# 130609_ReceiverSTM_0_0.net
KiCad netlist of a schematic drawn in EAGLE
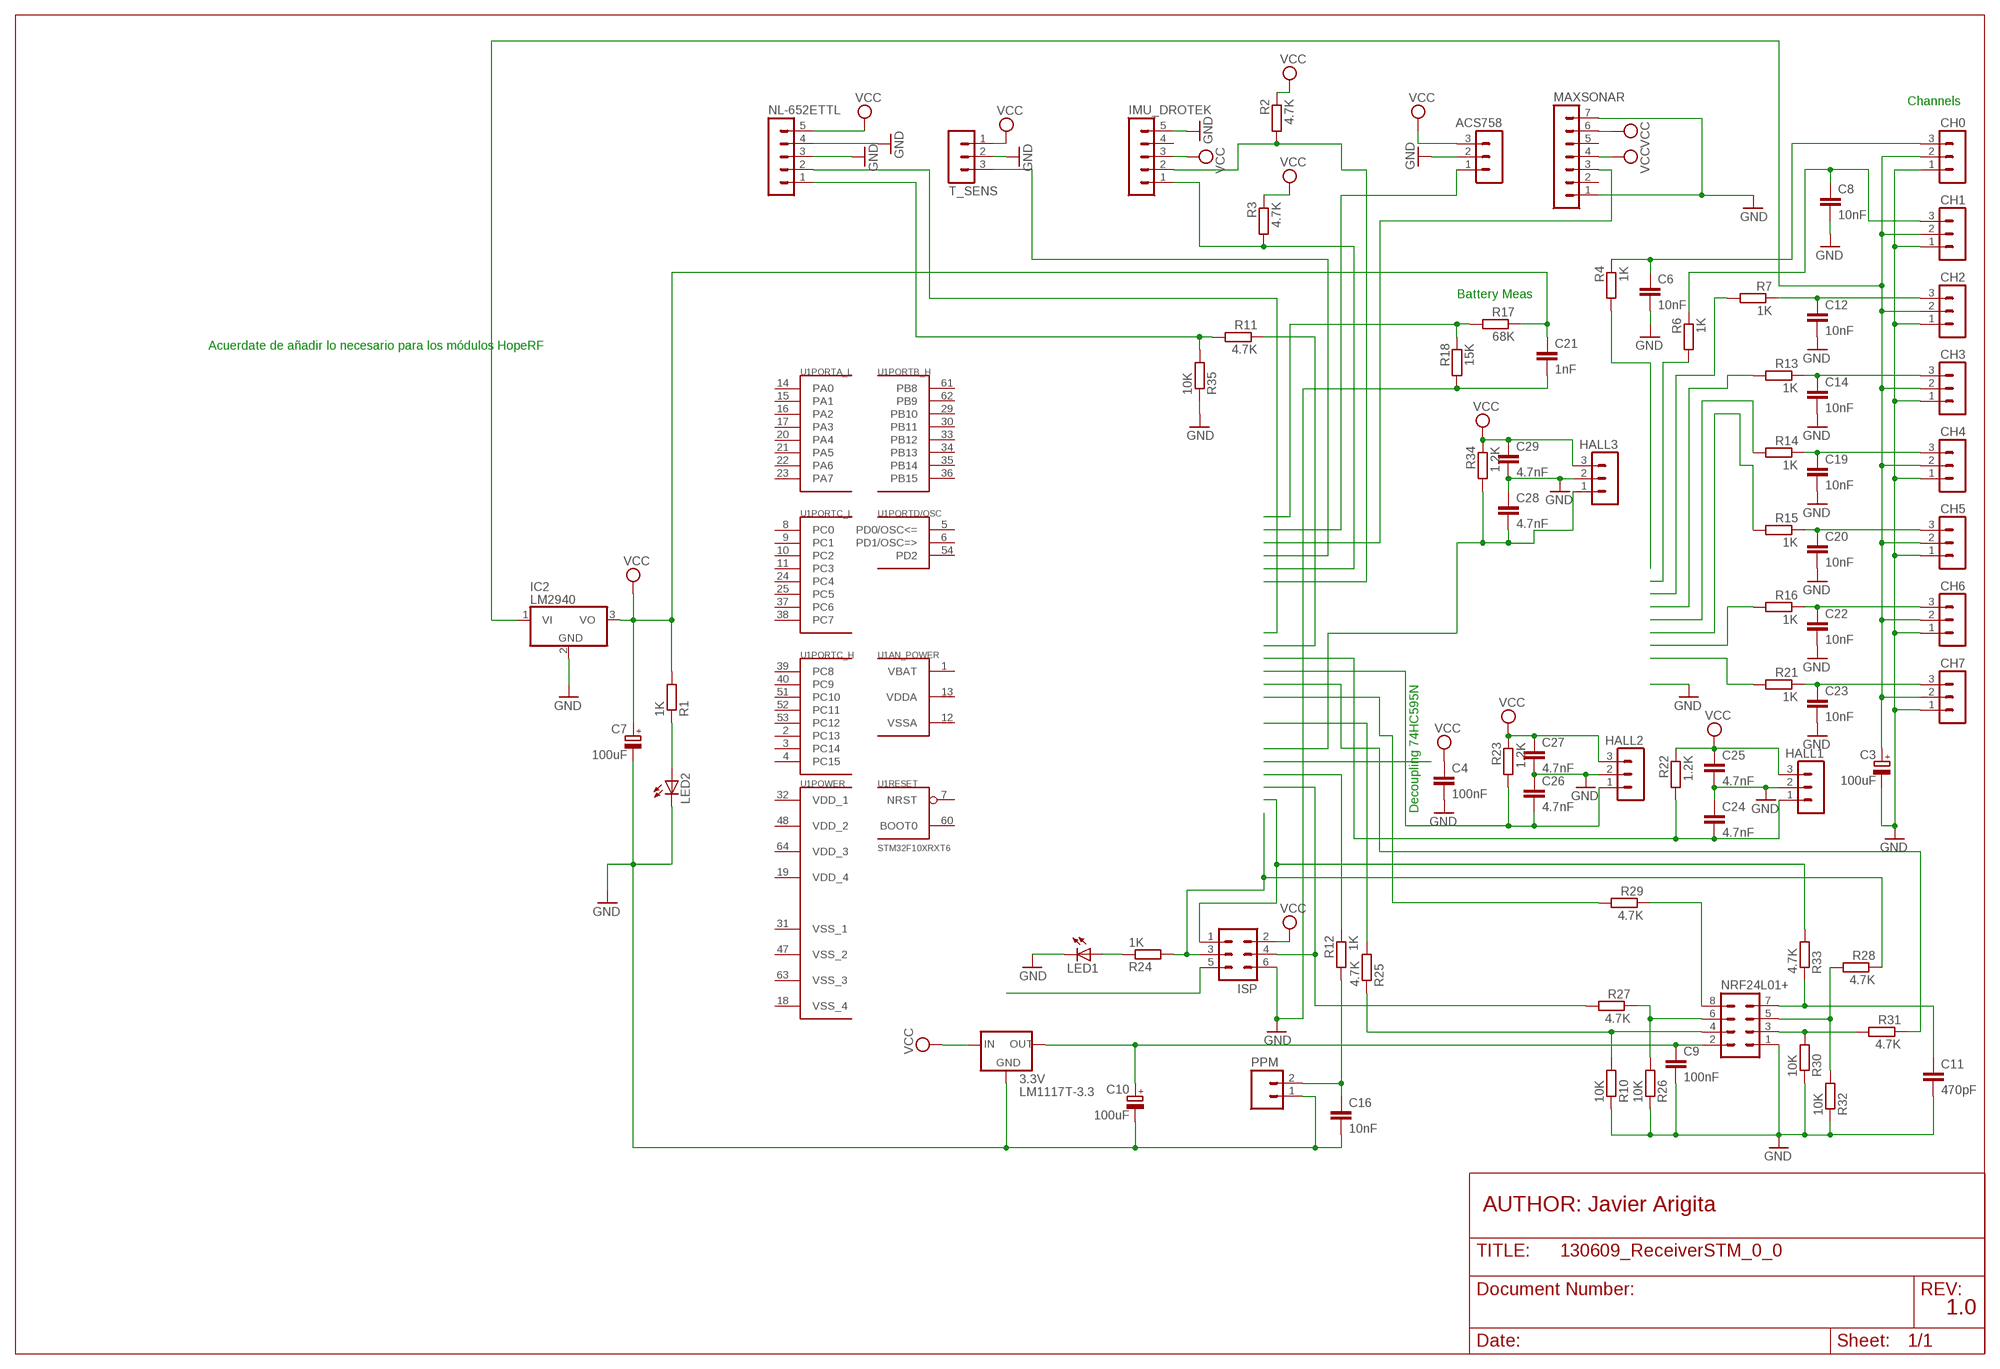
[diagram p0: schematic, sheet 1]

(export (version "E")
  (design (tool "Eeschema 10.0.6"))
  (components
    (comp (ref "3.3V")
      (value "LM1117T-3.3")
      (footprint "eagle-import:TO220")
      (libsource (lib "eagle-import") (part "LM1117T-3.3"))
    )
    (comp (ref "ACS758")
      (value "MA03-1")
      (footprint "eagle-import:MA03-1")
      (libsource (lib "eagle-import") (part "MA03-1"))
    )
    (comp (ref "C3")
      (value "100uF")
      (footprint "eagle-import:E2,5-6E")
      (libsource (lib "eagle-import") (part "CPOL-EUE2,5-6E"))
    )
    (comp (ref "C4")
      (value "100nF")
      (footprint "eagle-import:C050-025X075")
      (libsource (lib "eagle-import") (part "C-EU050-025X075"))
    )
    (comp (ref "C6")
      (value "10nF")
      (footprint "eagle-import:C025-030X050")
      (libsource (lib "eagle-import") (part "C-EU025-030X050"))
    )
    (comp (ref "C7")
      (value "100uF")
      (footprint "eagle-import:E2,5-6E")
      (libsource (lib "eagle-import") (part "CPOL-EUE2,5-6E"))
    )
    (comp (ref "C8")
      (value "10nF")
      (footprint "eagle-import:C025-030X050")
      (libsource (lib "eagle-import") (part "C-EU025-030X050"))
    )
    (comp (ref "C9")
      (value "100nF")
      (footprint "eagle-import:C050-025X075")
      (libsource (lib "eagle-import") (part "C-EU050-025X075"))
    )
    (comp (ref "C10")
      (value "100uF")
      (footprint "eagle-import:E2,5-6E")
      (libsource (lib "eagle-import") (part "CPOL-EUE2,5-6E"))
    )
    (comp (ref "C11")
      (value "470pF")
      (footprint "eagle-import:C025-030X050")
      (libsource (lib "eagle-import") (part "C-EU025-030X050"))
    )
    (comp (ref "C12")
      (value "10nF")
      (footprint "eagle-import:C025-030X050")
      (libsource (lib "eagle-import") (part "C-EU025-030X050"))
    )
    (comp (ref "C14")
      (value "10nF")
      (footprint "eagle-import:C025-030X050")
      (libsource (lib "eagle-import") (part "C-EU025-030X050"))
    )
    (comp (ref "C16")
      (value "10nF")
      (footprint "eagle-import:C025-030X050")
      (libsource (lib "eagle-import") (part "C-EU025-030X050"))
    )
    (comp (ref "C19")
      (value "10nF")
      (footprint "eagle-import:C025-030X050")
      (libsource (lib "eagle-import") (part "C-EU025-030X050"))
    )
    (comp (ref "C20")
      (value "10nF")
      (footprint "eagle-import:C025-030X050")
      (libsource (lib "eagle-import") (part "C-EU025-030X050"))
    )
    (comp (ref "C21")
      (value "1nF")
      (footprint "eagle-import:C050-025X075")
      (libsource (lib "eagle-import") (part "C-EU050-025X075"))
    )
    (comp (ref "C22")
      (value "10nF")
      (footprint "eagle-import:C025-030X050")
      (libsource (lib "eagle-import") (part "C-EU025-030X050"))
    )
    (comp (ref "C23")
      (value "10nF")
      (footprint "eagle-import:C025-030X050")
      (libsource (lib "eagle-import") (part "C-EU025-030X050"))
    )
    (comp (ref "C24")
      (value "4.7nF")
      (footprint "eagle-import:C025-030X050")
      (libsource (lib "eagle-import") (part "C-EU025-030X050"))
    )
    (comp (ref "C25")
      (value "4.7nF")
      (footprint "eagle-import:C025-030X050")
      (libsource (lib "eagle-import") (part "C-EU025-030X050"))
    )
    (comp (ref "C26")
      (value "4.7nF")
      (footprint "eagle-import:C025-030X050")
      (libsource (lib "eagle-import") (part "C-EU025-030X050"))
    )
    (comp (ref "C27")
      (value "4.7nF")
      (footprint "eagle-import:C025-030X050")
      (libsource (lib "eagle-import") (part "C-EU025-030X050"))
    )
    (comp (ref "C28")
      (value "4.7nF")
      (footprint "eagle-import:C025-030X050")
      (libsource (lib "eagle-import") (part "C-EU025-030X050"))
    )
    (comp (ref "C29")
      (value "4.7nF")
      (footprint "eagle-import:C025-030X050")
      (libsource (lib "eagle-import") (part "C-EU025-030X050"))
    )
    (comp (ref "CH0")
      (value "MA03-1")
      (footprint "eagle-import:MA03-1")
      (libsource (lib "eagle-import") (part "MA03-1"))
    )
    (comp (ref "CH1")
      (value "MA03-1")
      (footprint "eagle-import:MA03-1")
      (libsource (lib "eagle-import") (part "MA03-1"))
    )
    (comp (ref "CH2")
      (value "MA03-1")
      (footprint "eagle-import:MA03-1")
      (libsource (lib "eagle-import") (part "MA03-1"))
    )
    (comp (ref "CH3")
      (value "MA03-1")
      (footprint "eagle-import:MA03-1")
      (libsource (lib "eagle-import") (part "MA03-1"))
    )
    (comp (ref "CH4")
      (value "MA03-1")
      (footprint "eagle-import:MA03-1")
      (libsource (lib "eagle-import") (part "MA03-1"))
    )
    (comp (ref "CH5")
      (value "MA03-1")
      (footprint "eagle-import:MA03-1")
      (libsource (lib "eagle-import") (part "MA03-1"))
    )
    (comp (ref "CH6")
      (value "MA03-1")
      (footprint "eagle-import:MA03-1")
      (libsource (lib "eagle-import") (part "MA03-1"))
    )
    (comp (ref "CH7")
      (value "MA03-1")
      (footprint "eagle-import:MA03-1")
      (libsource (lib "eagle-import") (part "MA03-1"))
    )
    (comp (ref "HALL1")
      (value "MA03-1")
      (footprint "eagle-import:MA03-1")
      (libsource (lib "eagle-import") (part "MA03-1"))
    )
    (comp (ref "HALL2")
      (value "MA03-1")
      (footprint "eagle-import:MA03-1")
      (libsource (lib "eagle-import") (part "MA03-1"))
    )
    (comp (ref "HALL3")
      (value "MA03-1")
      (footprint "eagle-import:MA03-1")
      (libsource (lib "eagle-import") (part "MA03-1"))
    )
    (comp (ref "IC2")
      (value "LM2940")
      (footprint "eagle-import:TO220V")
      (libsource (lib "eagle-import") (part "LM2940"))
    )
    (comp (ref "IMU_DROTEK")
      (value "MA05-1")
      (footprint "eagle-import:MA05-1")
      (libsource (lib "eagle-import") (part "MA05-1"))
    )
    (comp (ref "ISP")
      (value "MA03-2")
      (footprint "eagle-import:MA03-2")
      (libsource (lib "eagle-import") (part "MA03-2"))
    )
    (comp (ref "LED1")
      (value "LED5MM")
      (footprint "eagle-import:LED5MM")
      (libsource (lib "eagle-import") (part "LED5MM"))
    )
    (comp (ref "LED2")
      (value "LED5MM")
      (footprint "eagle-import:LED5MM")
      (libsource (lib "eagle-import") (part "LED5MM"))
    )
    (comp (ref "MAXSONAR")
      (value "MA07-1")
      (footprint "eagle-import:MA07-1")
      (libsource (lib "eagle-import") (part "MA07-1"))
    )
    (comp (ref "NL-652ETTL")
      (value "MA05-1")
      (footprint "eagle-import:MA05-1")
      (fields (field (name "OC_FARNELL") "unknown") (field (name "OC_NEWARK") "unknown"))
      (libsource (lib "eagle-import") (part "MA05-1"))
    )
    (comp (ref "NRF24L01+")
      (value "MA04-2")
      (footprint "eagle-import:MA04-2")
      (libsource (lib "eagle-import") (part "MA04-2"))
    )
    (comp (ref "PPM")
      (value "M02")
      (footprint "eagle-import:02P")
      (libsource (lib "eagle-import") (part "M02"))
    )
    (comp (ref "R1")
      (value "1K")
      (footprint "eagle-import:0204_7")
      (libsource (lib "eagle-import") (part "R-EU_0204/7"))
    )
    (comp (ref "R2")
      (value "4.7K")
      (footprint "eagle-import:0204_7")
      (libsource (lib "eagle-import") (part "R-EU_0204/7"))
    )
    (comp (ref "R3")
      (value "4.7K")
      (footprint "eagle-import:0204_7")
      (libsource (lib "eagle-import") (part "R-EU_0204/7"))
    )
    (comp (ref "R4")
      (value "1K")
      (footprint "eagle-import:0204_7")
      (libsource (lib "eagle-import") (part "R-EU_0204/7"))
    )
    (comp (ref "R6")
      (value "1K")
      (footprint "eagle-import:0204_7")
      (libsource (lib "eagle-import") (part "R-EU_0204/7"))
    )
    (comp (ref "R7")
      (value "1K")
      (footprint "eagle-import:0204_7")
      (libsource (lib "eagle-import") (part "R-EU_0204/7"))
    )
    (comp (ref "R10")
      (value "10K")
      (footprint "eagle-import:0204_7")
      (libsource (lib "eagle-import") (part "R-EU_0204/7"))
    )
    (comp (ref "R11")
      (value "4.7K")
      (footprint "eagle-import:0204_7")
      (libsource (lib "eagle-import") (part "R-EU_0204/7"))
    )
    (comp (ref "R12")
      (value "1K")
      (footprint "eagle-import:0204_7")
      (libsource (lib "eagle-import") (part "R-EU_0204/7"))
    )
    (comp (ref "R13")
      (value "1K")
      (footprint "eagle-import:0204_7")
      (libsource (lib "eagle-import") (part "R-EU_0204/7"))
    )
    (comp (ref "R14")
      (value "1K")
      (footprint "eagle-import:0204_7")
      (libsource (lib "eagle-import") (part "R-EU_0204/7"))
    )
    (comp (ref "R15")
      (value "1K")
      (footprint "eagle-import:0204_7")
      (libsource (lib "eagle-import") (part "R-EU_0204/7"))
    )
    (comp (ref "R16")
      (value "1K")
      (footprint "eagle-import:0204_7")
      (libsource (lib "eagle-import") (part "R-EU_0204/7"))
    )
    (comp (ref "R17")
      (value "68K")
      (footprint "eagle-import:0204_7")
      (libsource (lib "eagle-import") (part "R-EU_0204/7"))
    )
    (comp (ref "R18")
      (value "15K")
      (footprint "eagle-import:0204_7")
      (libsource (lib "eagle-import") (part "R-EU_0204/7"))
    )
    (comp (ref "R21")
      (value "1K")
      (footprint "eagle-import:0204_7")
      (libsource (lib "eagle-import") (part "R-EU_0204/7"))
    )
    (comp (ref "R22")
      (value "1.2K")
      (footprint "eagle-import:0204_7")
      (libsource (lib "eagle-import") (part "R-EU_0204/7"))
    )
    (comp (ref "R23")
      (value "1.2K")
      (footprint "eagle-import:0204_7")
      (libsource (lib "eagle-import") (part "R-EU_0204/7"))
    )
    (comp (ref "R24")
      (value "1K")
      (footprint "eagle-import:0204_7")
      (libsource (lib "eagle-import") (part "R-EU_0204/7"))
    )
    (comp (ref "R25")
      (value "4.7K")
      (footprint "eagle-import:0204_7")
      (libsource (lib "eagle-import") (part "R-EU_0204/7"))
    )
    (comp (ref "R26")
      (value "10K")
      (footprint "eagle-import:0204_7")
      (libsource (lib "eagle-import") (part "R-EU_0204/7"))
    )
    (comp (ref "R27")
      (value "4.7K")
      (footprint "eagle-import:0204_7")
      (libsource (lib "eagle-import") (part "R-EU_0204/7"))
    )
    (comp (ref "R28")
      (value "4.7K")
      (footprint "eagle-import:0204_7")
      (libsource (lib "eagle-import") (part "R-EU_0204/7"))
    )
    (comp (ref "R29")
      (value "4.7K")
      (footprint "eagle-import:0204_7")
      (libsource (lib "eagle-import") (part "R-EU_0204/7"))
    )
    (comp (ref "R30")
      (value "10K")
      (footprint "eagle-import:0204_7")
      (libsource (lib "eagle-import") (part "R-EU_0204/7"))
    )
    (comp (ref "R31")
      (value "4.7K")
      (footprint "eagle-import:0204_7")
      (libsource (lib "eagle-import") (part "R-EU_0204/7"))
    )
    (comp (ref "R32")
      (value "10K")
      (footprint "eagle-import:0204_7")
      (libsource (lib "eagle-import") (part "R-EU_0204/7"))
    )
    (comp (ref "R33")
      (value "4.7K")
      (footprint "eagle-import:0204_7")
      (libsource (lib "eagle-import") (part "R-EU_0204/7"))
    )
    (comp (ref "R34")
      (value "1.2K")
      (footprint "eagle-import:0204_7")
      (libsource (lib "eagle-import") (part "R-EU_0204/7"))
    )
    (comp (ref "R35")
      (value "10K")
      (footprint "eagle-import:0204_7")
      (libsource (lib "eagle-import") (part "R-EU_0204/7"))
    )
    (comp (ref "T_SENS")
      (value "MA03-1")
      (footprint "eagle-import:MA03-1")
      (libsource (lib "eagle-import") (part "MA03-1"))
    )
    (comp (ref "U1")
      (value "STM32F10XRXT6")
      (footprint "eagle-import:TQFP64")
      (libsource (lib "eagle-import") (part "STM32F10XRXT6"))
    )
  )
  (nets
    (net (code "1") (name "/VBAT") (class "Default")
      (node (ref "U1") (pin "1") (pinfunction "VBAT_1") (pintype "power_in"))
    )
    (net (code "2") (name "/VDDA") (class "Default")
      (node (ref "U1") (pin "13") (pinfunction "VDDA_13") (pintype "power_in"))
    )
    (net (code "3") (name "/VDD_1") (class "Default")
      (node (ref "U1") (pin "32") (pinfunction "VDD_1_32") (pintype "power_in"))
    )
    (net (code "4") (name "/VDD_2") (class "Default")
      (node (ref "U1") (pin "48") (pinfunction "VDD_2_48") (pintype "power_in"))
    )
    (net (code "5") (name "/VDD_3") (class "Default")
      (node (ref "U1") (pin "64") (pinfunction "VDD_3_64") (pintype "power_in"))
    )
    (net (code "6") (name "/VDD_4") (class "Default")
      (node (ref "U1") (pin "19") (pinfunction "VDD_4_19") (pintype "power_in"))
    )
    (net (code "7") (name "/VSSA") (class "Default")
      (node (ref "U1") (pin "12") (pinfunction "VSSA_12") (pintype "power_in"))
    )
    (net (code "8") (name "/VSS_1") (class "Default")
      (node (ref "U1") (pin "31") (pinfunction "VSS_1_31") (pintype "power_in"))
    )
    (net (code "9") (name "/VSS_2") (class "Default")
      (node (ref "U1") (pin "47") (pinfunction "VSS_2_47") (pintype "power_in"))
    )
    (net (code "10") (name "/VSS_3") (class "Default")
      (node (ref "U1") (pin "63") (pinfunction "VSS_3_63") (pintype "power_in"))
    )
    (net (code "11") (name "/VSS_4") (class "Default")
      (node (ref "U1") (pin "18") (pinfunction "VSS_4_18") (pintype "power_in"))
    )
    (net (code "12") (name "GND") (class "Default")
      (node (ref "3.3V") (pin "1") (pinfunction "GND_1") (pintype "input"))
      (node (ref "ACS758") (pin "2") (pinfunction "2_2") (pintype "passive"))
      (node (ref "C10") (pin "-") (pinfunction "-_-") (pintype "passive"))
      (node (ref "C11") (pin "2") (pinfunction "2_2") (pintype "passive"))
      (node (ref "C12") (pin "2") (pinfunction "2_2") (pintype "passive"))
      (node (ref "C14") (pin "2") (pinfunction "2_2") (pintype "passive"))
      (node (ref "C16") (pin "2") (pinfunction "2_2") (pintype "passive"))
      (node (ref "C19") (pin "2") (pinfunction "2_2") (pintype "passive"))
      (node (ref "C20") (pin "2") (pinfunction "2_2") (pintype "passive"))
      (node (ref "C21") (pin "2") (pinfunction "2_2") (pintype "passive"))
      (node (ref "C22") (pin "2") (pinfunction "2_2") (pintype "passive"))
      (node (ref "C23") (pin "2") (pinfunction "2_2") (pintype "passive"))
      (node (ref "C24") (pin "1") (pinfunction "1_1") (pintype "passive"))
      (node (ref "C25") (pin "2") (pinfunction "2_2") (pintype "passive"))
      (node (ref "C26") (pin "1") (pinfunction "1_1") (pintype "passive"))
      (node (ref "C27") (pin "2") (pinfunction "2_2") (pintype "passive"))
      (node (ref "C28") (pin "1") (pinfunction "1_1") (pintype "passive"))
      (node (ref "C29") (pin "2") (pinfunction "2_2") (pintype "passive"))
      (node (ref "C3") (pin "-") (pinfunction "-_-") (pintype "passive"))
      (node (ref "C4") (pin "2") (pinfunction "2_2") (pintype "passive"))
      (node (ref "C6") (pin "2") (pinfunction "2_2") (pintype "passive"))
      (node (ref "C7") (pin "-") (pinfunction "-_-") (pintype "passive"))
      (node (ref "C8") (pin "2") (pinfunction "2_2") (pintype "passive"))
      (node (ref "C9") (pin "2") (pinfunction "2_2") (pintype "passive"))
      (node (ref "CH0") (pin "1") (pinfunction "1_1") (pintype "passive"))
      (node (ref "CH1") (pin "1") (pinfunction "1_1") (pintype "passive"))
      (node (ref "CH2") (pin "1") (pinfunction "1_1") (pintype "passive"))
      (node (ref "CH3") (pin "1") (pinfunction "1_1") (pintype "passive"))
      (node (ref "CH4") (pin "1") (pinfunction "1_1") (pintype "passive"))
      (node (ref "CH5") (pin "1") (pinfunction "1_1") (pintype "passive"))
      (node (ref "CH6") (pin "1") (pinfunction "1_1") (pintype "passive"))
      (node (ref "CH7") (pin "1") (pinfunction "1_1") (pintype "passive"))
      (node (ref "HALL1") (pin "2") (pinfunction "2_2") (pintype "passive"))
      (node (ref "HALL2") (pin "2") (pinfunction "2_2") (pintype "passive"))
      (node (ref "HALL3") (pin "2") (pinfunction "2_2") (pintype "passive"))
      (node (ref "IC2") (pin "2") (pinfunction "GND_2") (pintype "passive"))
      (node (ref "IMU_DROTEK") (pin "5") (pinfunction "5_5") (pintype "passive"))
      (node (ref "ISP") (pin "6") (pinfunction "6_6") (pintype "passive"))
      (node (ref "LED1") (pin "K") (pinfunction "C_K") (pintype "passive"))
      (node (ref "LED2") (pin "K") (pinfunction "C_K") (pintype "passive"))
      (node (ref "MAXSONAR") (pin "1") (pinfunction "1_1") (pintype "passive"))
      (node (ref "MAXSONAR") (pin "7") (pinfunction "7_7") (pintype "passive"))
      (node (ref "NL-652ETTL") (pin "3") (pinfunction "3_3") (pintype "passive"))
      (node (ref "NL-652ETTL") (pin "4") (pinfunction "4_4") (pintype "passive"))
      (node (ref "NRF24L01+") (pin "1") (pinfunction "1_1") (pintype "passive"))
      (node (ref "PPM") (pin "1") (pinfunction "1_1") (pintype "passive"))
      (node (ref "R10") (pin "1") (pinfunction "1_1") (pintype "passive"))
      (node (ref "R18") (pin "2") (pinfunction "2_2") (pintype "passive"))
      (node (ref "R26") (pin "1") (pinfunction "1_1") (pintype "passive"))
      (node (ref "R30") (pin "1") (pinfunction "1_1") (pintype "passive"))
      (node (ref "R32") (pin "1") (pinfunction "1_1") (pintype "passive"))
      (node (ref "R35") (pin "1") (pinfunction "1_1") (pintype "passive"))
      (node (ref "T_SENS") (pin "2") (pinfunction "2_2") (pintype "passive"))
    )
    (net (code "13") (name "Net-(3.3V-OUT)") (class "Default")
      (node (ref "3.3V") (pin "2") (pinfunction "OUT_2") (pintype "passive"))
      (node (ref "C10") (pin "+") (pinfunction "+_+") (pintype "passive"))
      (node (ref "C9") (pin "1") (pinfunction "1_1") (pintype "passive"))
      (node (ref "NRF24L01+") (pin "2") (pinfunction "2_2") (pintype "passive"))
    )
    (net (code "14") (name "Net-(C6-Pad1)") (class "Default")
      (node (ref "C6") (pin "1") (pinfunction "1_1") (pintype "passive"))
      (node (ref "CH0") (pin "3") (pinfunction "3_3") (pintype "passive"))
      (node (ref "R4") (pin "1") (pinfunction "1_1") (pintype "passive"))
    )
    (net (code "15") (name "Net-(C8-Pad1)") (class "Default")
      (node (ref "C8") (pin "1") (pinfunction "1_1") (pintype "passive"))
      (node (ref "CH1") (pin "3") (pinfunction "3_3") (pintype "passive"))
      (node (ref "R6") (pin "1") (pinfunction "1_1") (pintype "passive"))
    )
    (net (code "16") (name "Net-(C11-Pad1)") (class "Default")
      (node (ref "C11") (pin "1") (pinfunction "1_1") (pintype "passive"))
      (node (ref "NRF24L01+") (pin "7") (pinfunction "7_7") (pintype "passive"))
      (node (ref "R33") (pin "1") (pinfunction "1_1") (pintype "passive"))
    )
    (net (code "17") (name "Net-(C12-Pad1)") (class "Default")
      (node (ref "C12") (pin "1") (pinfunction "1_1") (pintype "passive"))
      (node (ref "CH2") (pin "3") (pinfunction "3_3") (pintype "passive"))
      (node (ref "R7") (pin "1") (pinfunction "1_1") (pintype "passive"))
    )
    (net (code "18") (name "Net-(C14-Pad1)") (class "Default")
      (node (ref "C14") (pin "1") (pinfunction "1_1") (pintype "passive"))
      (node (ref "CH3") (pin "3") (pinfunction "3_3") (pintype "passive"))
      (node (ref "R13") (pin "1") (pinfunction "1_1") (pintype "passive"))
    )
    (net (code "19") (name "Net-(C16-Pad1)") (class "Default")
      (node (ref "C16") (pin "1") (pinfunction "1_1") (pintype "passive"))
      (node (ref "PPM") (pin "2") (pinfunction "2_2") (pintype "passive"))
      (node (ref "R12") (pin "2") (pinfunction "2_2") (pintype "passive"))
    )
    (net (code "20") (name "Net-(C19-Pad1)") (class "Default")
      (node (ref "C19") (pin "1") (pinfunction "1_1") (pintype "passive"))
      (node (ref "CH4") (pin "3") (pinfunction "3_3") (pintype "passive"))
      (node (ref "R14") (pin "1") (pinfunction "1_1") (pintype "passive"))
    )
    (net (code "21") (name "Net-(C20-Pad1)") (class "Default")
      (node (ref "C20") (pin "1") (pinfunction "1_1") (pintype "passive"))
      (node (ref "CH5") (pin "3") (pinfunction "3_3") (pintype "passive"))
      (node (ref "R15") (pin "1") (pinfunction "1_1") (pintype "passive"))
    )
    (net (code "22") (name "Net-(C22-Pad1)") (class "Default")
      (node (ref "C22") (pin "1") (pinfunction "1_1") (pintype "passive"))
      (node (ref "CH6") (pin "3") (pinfunction "3_3") (pintype "passive"))
      (node (ref "R16") (pin "1") (pinfunction "1_1") (pintype "passive"))
    )
    (net (code "23") (name "Net-(C23-Pad1)") (class "Default")
      (node (ref "C23") (pin "1") (pinfunction "1_1") (pintype "passive"))
      (node (ref "CH7") (pin "3") (pinfunction "3_3") (pintype "passive"))
      (node (ref "R21") (pin "1") (pinfunction "1_1") (pintype "passive"))
    )
    (net (code "24") (name "Net-(C24-Pad2)") (class "Default")
      (node (ref "C24") (pin "2") (pinfunction "2_2") (pintype "passive"))
      (node (ref "HALL1") (pin "1") (pinfunction "1_1") (pintype "passive"))
      (node (ref "R22") (pin "2") (pinfunction "2_2") (pintype "passive"))
    )
    (net (code "25") (name "Net-(C26-Pad2)") (class "Default")
      (node (ref "C26") (pin "2") (pinfunction "2_2") (pintype "passive"))
      (node (ref "HALL2") (pin "1") (pinfunction "1_1") (pintype "passive"))
      (node (ref "R23") (pin "2") (pinfunction "2_2") (pintype "passive"))
    )
    (net (code "26") (name "Net-(C28-Pad2)") (class "Default")
      (node (ref "C28") (pin "2") (pinfunction "2_2") (pintype "passive"))
      (node (ref "HALL3") (pin "1") (pinfunction "1_1") (pintype "passive"))
      (node (ref "R34") (pin "2") (pinfunction "2_2") (pintype "passive"))
    )
    (net (code "27") (name "Net-(IC2-VI)") (class "Default")
      (node (ref "C3") (pin "+") (pinfunction "+_+") (pintype "passive"))
      (node (ref "CH0") (pin "2") (pinfunction "2_2") (pintype "passive"))
      (node (ref "CH1") (pin "2") (pinfunction "2_2") (pintype "passive"))
      (node (ref "CH2") (pin "2") (pinfunction "2_2") (pintype "passive"))
      (node (ref "CH3") (pin "2") (pinfunction "2_2") (pintype "passive"))
      (node (ref "CH4") (pin "2") (pinfunction "2_2") (pintype "passive"))
      (node (ref "CH5") (pin "2") (pinfunction "2_2") (pintype "passive"))
      (node (ref "CH6") (pin "2") (pinfunction "2_2") (pintype "passive"))
      (node (ref "CH7") (pin "2") (pinfunction "2_2") (pintype "passive"))
      (node (ref "IC2") (pin "1") (pinfunction "VI_1") (pintype "input"))
    )
    (net (code "28") (name "Net-(IMU_DROTEK-Pad1)") (class "Default")
      (node (ref "IMU_DROTEK") (pin "1") (pinfunction "1_1") (pintype "passive"))
      (node (ref "R3") (pin "2") (pinfunction "2_2") (pintype "passive"))
    )
    (net (code "29") (name "Net-(IMU_DROTEK-Pad2)") (class "Default")
      (node (ref "IMU_DROTEK") (pin "2") (pinfunction "2_2") (pintype "passive"))
      (node (ref "R2") (pin "2") (pinfunction "2_2") (pintype "passive"))
    )
    (net (code "30") (name "Net-(ISP-Pad1)") (class "Default")
      (node (ref "ISP") (pin "1") (pinfunction "1_1") (pintype "passive"))
      (node (ref "R33") (pin "2") (pinfunction "2_2") (pintype "passive"))
    )
    (net (code "31") (name "Net-(ISP-Pad3)") (class "Default")
      (node (ref "ISP") (pin "3") (pinfunction "3_3") (pintype "passive"))
      (node (ref "R24") (pin "2") (pinfunction "2_2") (pintype "passive"))
      (node (ref "R28") (pin "1") (pinfunction "1_1") (pintype "passive"))
    )
    (net (code "32") (name "Net-(ISP-Pad4)") (class "Default")
      (node (ref "ISP") (pin "4") (pinfunction "4_4") (pintype "passive"))
      (node (ref "R27") (pin "2") (pinfunction "2_2") (pintype "passive"))
    )
    (net (code "33") (name "Net-(LED1-PadA)") (class "Default")
      (node (ref "LED1") (pin "A") (pinfunction "A_A") (pintype "passive"))
      (node (ref "R24") (pin "1") (pinfunction "1_1") (pintype "passive"))
    )
    (net (code "34") (name "Net-(LED2-PadA)") (class "Default")
      (node (ref "LED2") (pin "A") (pinfunction "A_A") (pintype "passive"))
      (node (ref "R1") (pin "1") (pinfunction "1_1") (pintype "passive"))
    )
    (net (code "35") (name "Net-(NL-652ETTL-Pad1)") (class "Default")
      (node (ref "NL-652ETTL") (pin "1") (pinfunction "1_1") (pintype "passive"))
      (node (ref "R11") (pin "2") (pinfunction "2_2") (pintype "passive"))
      (node (ref "R35") (pin "2") (pinfunction "2_2") (pintype "passive"))
    )
    (net (code "36") (name "Net-(NRF24L01+-Pad3)") (class "Default")
      (node (ref "NRF24L01+") (pin "3") (pinfunction "3_3") (pintype "passive"))
      (node (ref "R30") (pin "2") (pinfunction "2_2") (pintype "passive"))
      (node (ref "R31") (pin "2") (pinfunction "2_2") (pintype "passive"))
    )
    (net (code "37") (name "Net-(NRF24L01+-Pad4)") (class "Default")
      (node (ref "NRF24L01+") (pin "4") (pinfunction "4_4") (pintype "passive"))
      (node (ref "R10") (pin "2") (pinfunction "2_2") (pintype "passive"))
      (node (ref "R25") (pin "1") (pinfunction "1_1") (pintype "passive"))
    )
    (net (code "38") (name "Net-(NRF24L01+-Pad5)") (class "Default")
      (node (ref "NRF24L01+") (pin "5") (pinfunction "5_5") (pintype "passive"))
      (node (ref "R28") (pin "2") (pinfunction "2_2") (pintype "passive"))
      (node (ref "R32") (pin "2") (pinfunction "2_2") (pintype "passive"))
    )
    (net (code "39") (name "Net-(NRF24L01+-Pad6)") (class "Default")
      (node (ref "NRF24L01+") (pin "6") (pinfunction "6_6") (pintype "passive"))
      (node (ref "R26") (pin "2") (pinfunction "2_2") (pintype "passive"))
      (node (ref "R27") (pin "1") (pinfunction "1_1") (pintype "passive"))
    )
    (net (code "40") (name "Net-(NRF24L01+-Pad8)") (class "Default")
      (node (ref "NRF24L01+") (pin "8") (pinfunction "8_8") (pintype "passive"))
      (node (ref "R29") (pin "1") (pinfunction "1_1") (pintype "passive"))
    )
    (net (code "41") (name "Net-(R17-Pad2)") (class "Default")
      (node (ref "R17") (pin "2") (pinfunction "2_2") (pintype "passive"))
      (node (ref "R18") (pin "1") (pinfunction "1_1") (pintype "passive"))
    )
    (net (code "42") (name "VCC") (class "Default")
      (node (ref "3.3V") (pin "3") (pinfunction "IN_3") (pintype "input"))
      (node (ref "ACS758") (pin "3") (pinfunction "3_3") (pintype "passive"))
      (node (ref "C21") (pin "1") (pinfunction "1_1") (pintype "passive"))
      (node (ref "C25") (pin "1") (pinfunction "1_1") (pintype "passive"))
      (node (ref "C27") (pin "1") (pinfunction "1_1") (pintype "passive"))
      (node (ref "C29") (pin "1") (pinfunction "1_1") (pintype "passive"))
      (node (ref "C4") (pin "1") (pinfunction "1_1") (pintype "passive"))
      (node (ref "C7") (pin "+") (pinfunction "+_+") (pintype "passive"))
      (node (ref "HALL1") (pin "3") (pinfunction "3_3") (pintype "passive"))
      (node (ref "HALL2") (pin "3") (pinfunction "3_3") (pintype "passive"))
      (node (ref "HALL3") (pin "3") (pinfunction "3_3") (pintype "passive"))
      (node (ref "IC2") (pin "3") (pinfunction "VO_3") (pintype "passive"))
      (node (ref "IMU_DROTEK") (pin "3") (pinfunction "3_3") (pintype "passive"))
      (node (ref "ISP") (pin "2") (pinfunction "2_2") (pintype "passive"))
      (node (ref "MAXSONAR") (pin "4") (pinfunction "4_4") (pintype "passive"))
      (node (ref "MAXSONAR") (pin "6") (pinfunction "6_6") (pintype "passive"))
      (node (ref "NL-652ETTL") (pin "5") (pinfunction "5_5") (pintype "passive"))
      (node (ref "R1") (pin "2") (pinfunction "2_2") (pintype "passive"))
      (node (ref "R17") (pin "1") (pinfunction "1_1") (pintype "passive"))
      (node (ref "R2") (pin "1") (pinfunction "1_1") (pintype "passive"))
      (node (ref "R22") (pin "1") (pinfunction "1_1") (pintype "passive"))
      (node (ref "R23") (pin "1") (pinfunction "1_1") (pintype "passive"))
      (node (ref "R3") (pin "1") (pinfunction "1_1") (pintype "passive"))
      (node (ref "R34") (pin "1") (pinfunction "1_1") (pintype "passive"))
      (node (ref "T_SENS") (pin "1") (pinfunction "1_1") (pintype "passive"))
    )
    (net (code "43") (name "unconnected-(ACS758-Pad1)") (class "Default")
      (node (ref "ACS758") (pin "1") (pinfunction "1_1") (pintype "passive"))
    )
    (net (code "44") (name "unconnected-(IMU_DROTEK-Pad4)") (class "Default")
      (node (ref "IMU_DROTEK") (pin "4") (pinfunction "4_4") (pintype "passive"))
    )
    (net (code "45") (name "unconnected-(ISP-Pad5)") (class "Default")
      (node (ref "ISP") (pin "5") (pinfunction "5_5") (pintype "passive"))
    )
    (net (code "46") (name "unconnected-(MAXSONAR-Pad2)") (class "Default")
      (node (ref "MAXSONAR") (pin "2") (pinfunction "2_2") (pintype "passive"))
    )
    (net (code "47") (name "unconnected-(MAXSONAR-Pad3)") (class "Default")
      (node (ref "MAXSONAR") (pin "3") (pinfunction "3_3") (pintype "passive"))
    )
    (net (code "48") (name "unconnected-(MAXSONAR-Pad5)") (class "Default")
      (node (ref "MAXSONAR") (pin "5") (pinfunction "5_5") (pintype "passive"))
    )
    (net (code "49") (name "unconnected-(NL-652ETTL-Pad2)") (class "Default")
      (node (ref "NL-652ETTL") (pin "2") (pinfunction "2_2") (pintype "passive"))
    )
    (net (code "50") (name "unconnected-(R4-Pad2)") (class "Default")
      (node (ref "R4") (pin "2") (pinfunction "2_2") (pintype "passive"))
    )
    (net (code "51") (name "unconnected-(R6-Pad2)") (class "Default")
      (node (ref "R6") (pin "2") (pinfunction "2_2") (pintype "passive"))
    )
    (net (code "52") (name "unconnected-(R7-Pad2)") (class "Default")
      (node (ref "R7") (pin "2") (pinfunction "2_2") (pintype "passive"))
    )
    (net (code "53") (name "unconnected-(R11-Pad1)") (class "Default")
      (node (ref "R11") (pin "1") (pinfunction "1_1") (pintype "passive"))
    )
    (net (code "54") (name "unconnected-(R12-Pad1)") (class "Default")
      (node (ref "R12") (pin "1") (pinfunction "1_1") (pintype "passive"))
    )
    (net (code "55") (name "unconnected-(R13-Pad2)") (class "Default")
      (node (ref "R13") (pin "2") (pinfunction "2_2") (pintype "passive"))
    )
    (net (code "56") (name "unconnected-(R14-Pad2)") (class "Default")
      (node (ref "R14") (pin "2") (pinfunction "2_2") (pintype "passive"))
    )
    (net (code "57") (name "unconnected-(R15-Pad2)") (class "Default")
      (node (ref "R15") (pin "2") (pinfunction "2_2") (pintype "passive"))
    )
    (net (code "58") (name "unconnected-(R16-Pad2)") (class "Default")
      (node (ref "R16") (pin "2") (pinfunction "2_2") (pintype "passive"))
    )
    (net (code "59") (name "unconnected-(R21-Pad2)") (class "Default")
      (node (ref "R21") (pin "2") (pinfunction "2_2") (pintype "passive"))
    )
    (net (code "60") (name "unconnected-(R25-Pad2)") (class "Default")
      (node (ref "R25") (pin "2") (pinfunction "2_2") (pintype "passive"))
    )
    (net (code "61") (name "unconnected-(R29-Pad2)") (class "Default")
      (node (ref "R29") (pin "2") (pinfunction "2_2") (pintype "passive"))
    )
    (net (code "62") (name "unconnected-(R31-Pad1)") (class "Default")
      (node (ref "R31") (pin "1") (pinfunction "1_1") (pintype "passive"))
    )
    (net (code "63") (name "unconnected-(T_SENS-Pad3)") (class "Default")
      (node (ref "T_SENS") (pin "3") (pinfunction "3_3") (pintype "passive"))
    )
    (net (code "64") (name "unconnected-(U1C-PA0-Pad14)") (class "Default")
      (node (ref "U1") (pin "14") (pinfunction "PA0_14") (pintype "bidirectional"))
    )
    (net (code "65") (name "unconnected-(U1C-PA1-Pad15)") (class "Default")
      (node (ref "U1") (pin "15") (pinfunction "PA1_15") (pintype "bidirectional"))
    )
    (net (code "66") (name "unconnected-(U1C-PA2-Pad16)") (class "Default")
      (node (ref "U1") (pin "16") (pinfunction "PA2_16") (pintype "bidirectional"))
    )
    (net (code "67") (name "unconnected-(U1C-PA3-Pad17)") (class "Default")
      (node (ref "U1") (pin "17") (pinfunction "PA3_17") (pintype "bidirectional"))
    )
    (net (code "68") (name "unconnected-(U1C-PA4-Pad20)") (class "Default")
      (node (ref "U1") (pin "20") (pinfunction "PA4_20") (pintype "bidirectional"))
    )
    (net (code "69") (name "unconnected-(U1C-PA5-Pad21)") (class "Default")
      (node (ref "U1") (pin "21") (pinfunction "PA5_21") (pintype "bidirectional"))
    )
    (net (code "70") (name "unconnected-(U1C-PA6-Pad22)") (class "Default")
      (node (ref "U1") (pin "22") (pinfunction "PA6_22") (pintype "bidirectional"))
    )
    (net (code "71") (name "unconnected-(U1C-PA7-Pad23)") (class "Default")
      (node (ref "U1") (pin "23") (pinfunction "PA7_23") (pintype "bidirectional"))
    )
    (net (code "72") (name "unconnected-(U1D-PB8-Pad61)") (class "Default")
      (node (ref "U1") (pin "61") (pinfunction "PB8_61") (pintype "bidirectional"))
    )
    (net (code "73") (name "unconnected-(U1D-PB9-Pad62)") (class "Default")
      (node (ref "U1") (pin "62") (pinfunction "PB9_62") (pintype "bidirectional"))
    )
    (net (code "74") (name "unconnected-(U1D-PB10-Pad29)") (class "Default")
      (node (ref "U1") (pin "29") (pinfunction "PB10_29") (pintype "bidirectional"))
    )
    (net (code "75") (name "unconnected-(U1D-PB11-Pad30)") (class "Default")
      (node (ref "U1") (pin "30") (pinfunction "PB11_30") (pintype "bidirectional"))
    )
    (net (code "76") (name "unconnected-(U1D-PB12-Pad33)") (class "Default")
      (node (ref "U1") (pin "33") (pinfunction "PB12_33") (pintype "bidirectional"))
    )
    (net (code "77") (name "unconnected-(U1D-PB13-Pad34)") (class "Default")
      (node (ref "U1") (pin "34") (pinfunction "PB13_34") (pintype "bidirectional"))
    )
    (net (code "78") (name "unconnected-(U1D-PB14-Pad35)") (class "Default")
      (node (ref "U1") (pin "35") (pinfunction "PB14_35") (pintype "bidirectional"))
    )
    (net (code "79") (name "unconnected-(U1D-PB15-Pad36)") (class "Default")
      (node (ref "U1") (pin "36") (pinfunction "PB15_36") (pintype "bidirectional"))
    )
    (net (code "80") (name "unconnected-(U1F-PC8-Pad39)") (class "Default")
      (node (ref "U1") (pin "39") (pinfunction "PC8_39") (pintype "bidirectional"))
    )
    (net (code "81") (name "unconnected-(U1F-PC9-Pad40)") (class "Default")
      (node (ref "U1") (pin "40") (pinfunction "PC9_40") (pintype "bidirectional"))
    )
    (net (code "82") (name "unconnected-(U1F-PC10-Pad51)") (class "Default")
      (node (ref "U1") (pin "51") (pinfunction "PC10_51") (pintype "bidirectional"))
    )
    (net (code "83") (name "unconnected-(U1F-PC11-Pad52)") (class "Default")
      (node (ref "U1") (pin "52") (pinfunction "PC11_52") (pintype "bidirectional"))
    )
    (net (code "84") (name "unconnected-(U1F-PC12-Pad53)") (class "Default")
      (node (ref "U1") (pin "53") (pinfunction "PC12_53") (pintype "bidirectional"))
    )
    (net (code "85") (name "unconnected-(U1F-PC13-Pad2)") (class "Default")
      (node (ref "U1") (pin "2") (pinfunction "PC13_2") (pintype "bidirectional"))
    )
    (net (code "86") (name "unconnected-(U1F-PC14-Pad3)") (class "Default")
      (node (ref "U1") (pin "3") (pinfunction "PC14_3") (pintype "bidirectional"))
    )
    (net (code "87") (name "unconnected-(U1F-PC15-Pad4)") (class "Default")
      (node (ref "U1") (pin "4") (pinfunction "PC15_4") (pintype "bidirectional"))
    )
    (net (code "88") (name "unconnected-(U1G-PC0-Pad8)") (class "Default")
      (node (ref "U1") (pin "8") (pinfunction "PC0_8") (pintype "bidirectional"))
    )
    (net (code "89") (name "unconnected-(U1G-PC1-Pad9)") (class "Default")
      (node (ref "U1") (pin "9") (pinfunction "PC1_9") (pintype "bidirectional"))
    )
    (net (code "90") (name "unconnected-(U1G-PC2-Pad10)") (class "Default")
      (node (ref "U1") (pin "10") (pinfunction "PC2_10") (pintype "bidirectional"))
    )
    (net (code "91") (name "unconnected-(U1G-PC3-Pad11)") (class "Default")
      (node (ref "U1") (pin "11") (pinfunction "PC3_11") (pintype "bidirectional"))
    )
    (net (code "92") (name "unconnected-(U1G-PC4-Pad24)") (class "Default")
      (node (ref "U1") (pin "24") (pinfunction "PC4_24") (pintype "bidirectional"))
    )
    (net (code "93") (name "unconnected-(U1G-PC5-Pad25)") (class "Default")
      (node (ref "U1") (pin "25") (pinfunction "PC5_25") (pintype "bidirectional"))
    )
    (net (code "94") (name "unconnected-(U1G-PC6-Pad37)") (class "Default")
      (node (ref "U1") (pin "37") (pinfunction "PC6_37") (pintype "bidirectional"))
    )
    (net (code "95") (name "unconnected-(U1G-PC7-Pad38)") (class "Default")
      (node (ref "U1") (pin "38") (pinfunction "PC7_38") (pintype "bidirectional"))
    )
    (net (code "96") (name "unconnected-(U1H-PD0{slash}OSC<=-Pad5)") (class "Default")
      (node (ref "U1") (pin "5") (pinfunction "PD0/OSC<=_5") (pintype "bidirectional"))
    )
    (net (code "97") (name "unconnected-(U1H-PD1{slash}OSC=>-Pad6)") (class "Default")
      (node (ref "U1") (pin "6") (pinfunction "PD1/OSC=>_6") (pintype "bidirectional"))
    )
    (net (code "98") (name "unconnected-(U1H-PD2-Pad54)") (class "Default")
      (node (ref "U1") (pin "54") (pinfunction "PD2_54") (pintype "bidirectional"))
    )
    (net (code "99") (name "unconnected-(U1J-BOOT0-Pad60)") (class "Default")
      (node (ref "U1") (pin "60") (pinfunction "BOOT0_60") (pintype "input"))
    )
    (net (code "100") (name "unconnected-(U1J-NRST-Pad7)") (class "Default")
      (node (ref "U1") (pin "7") (pinfunction "NRST_7") (pintype "input"))
    )
  )
)
